# LPCB235_-_DAC.net
KiCad netlist of a schematic drawn in Altium Designer
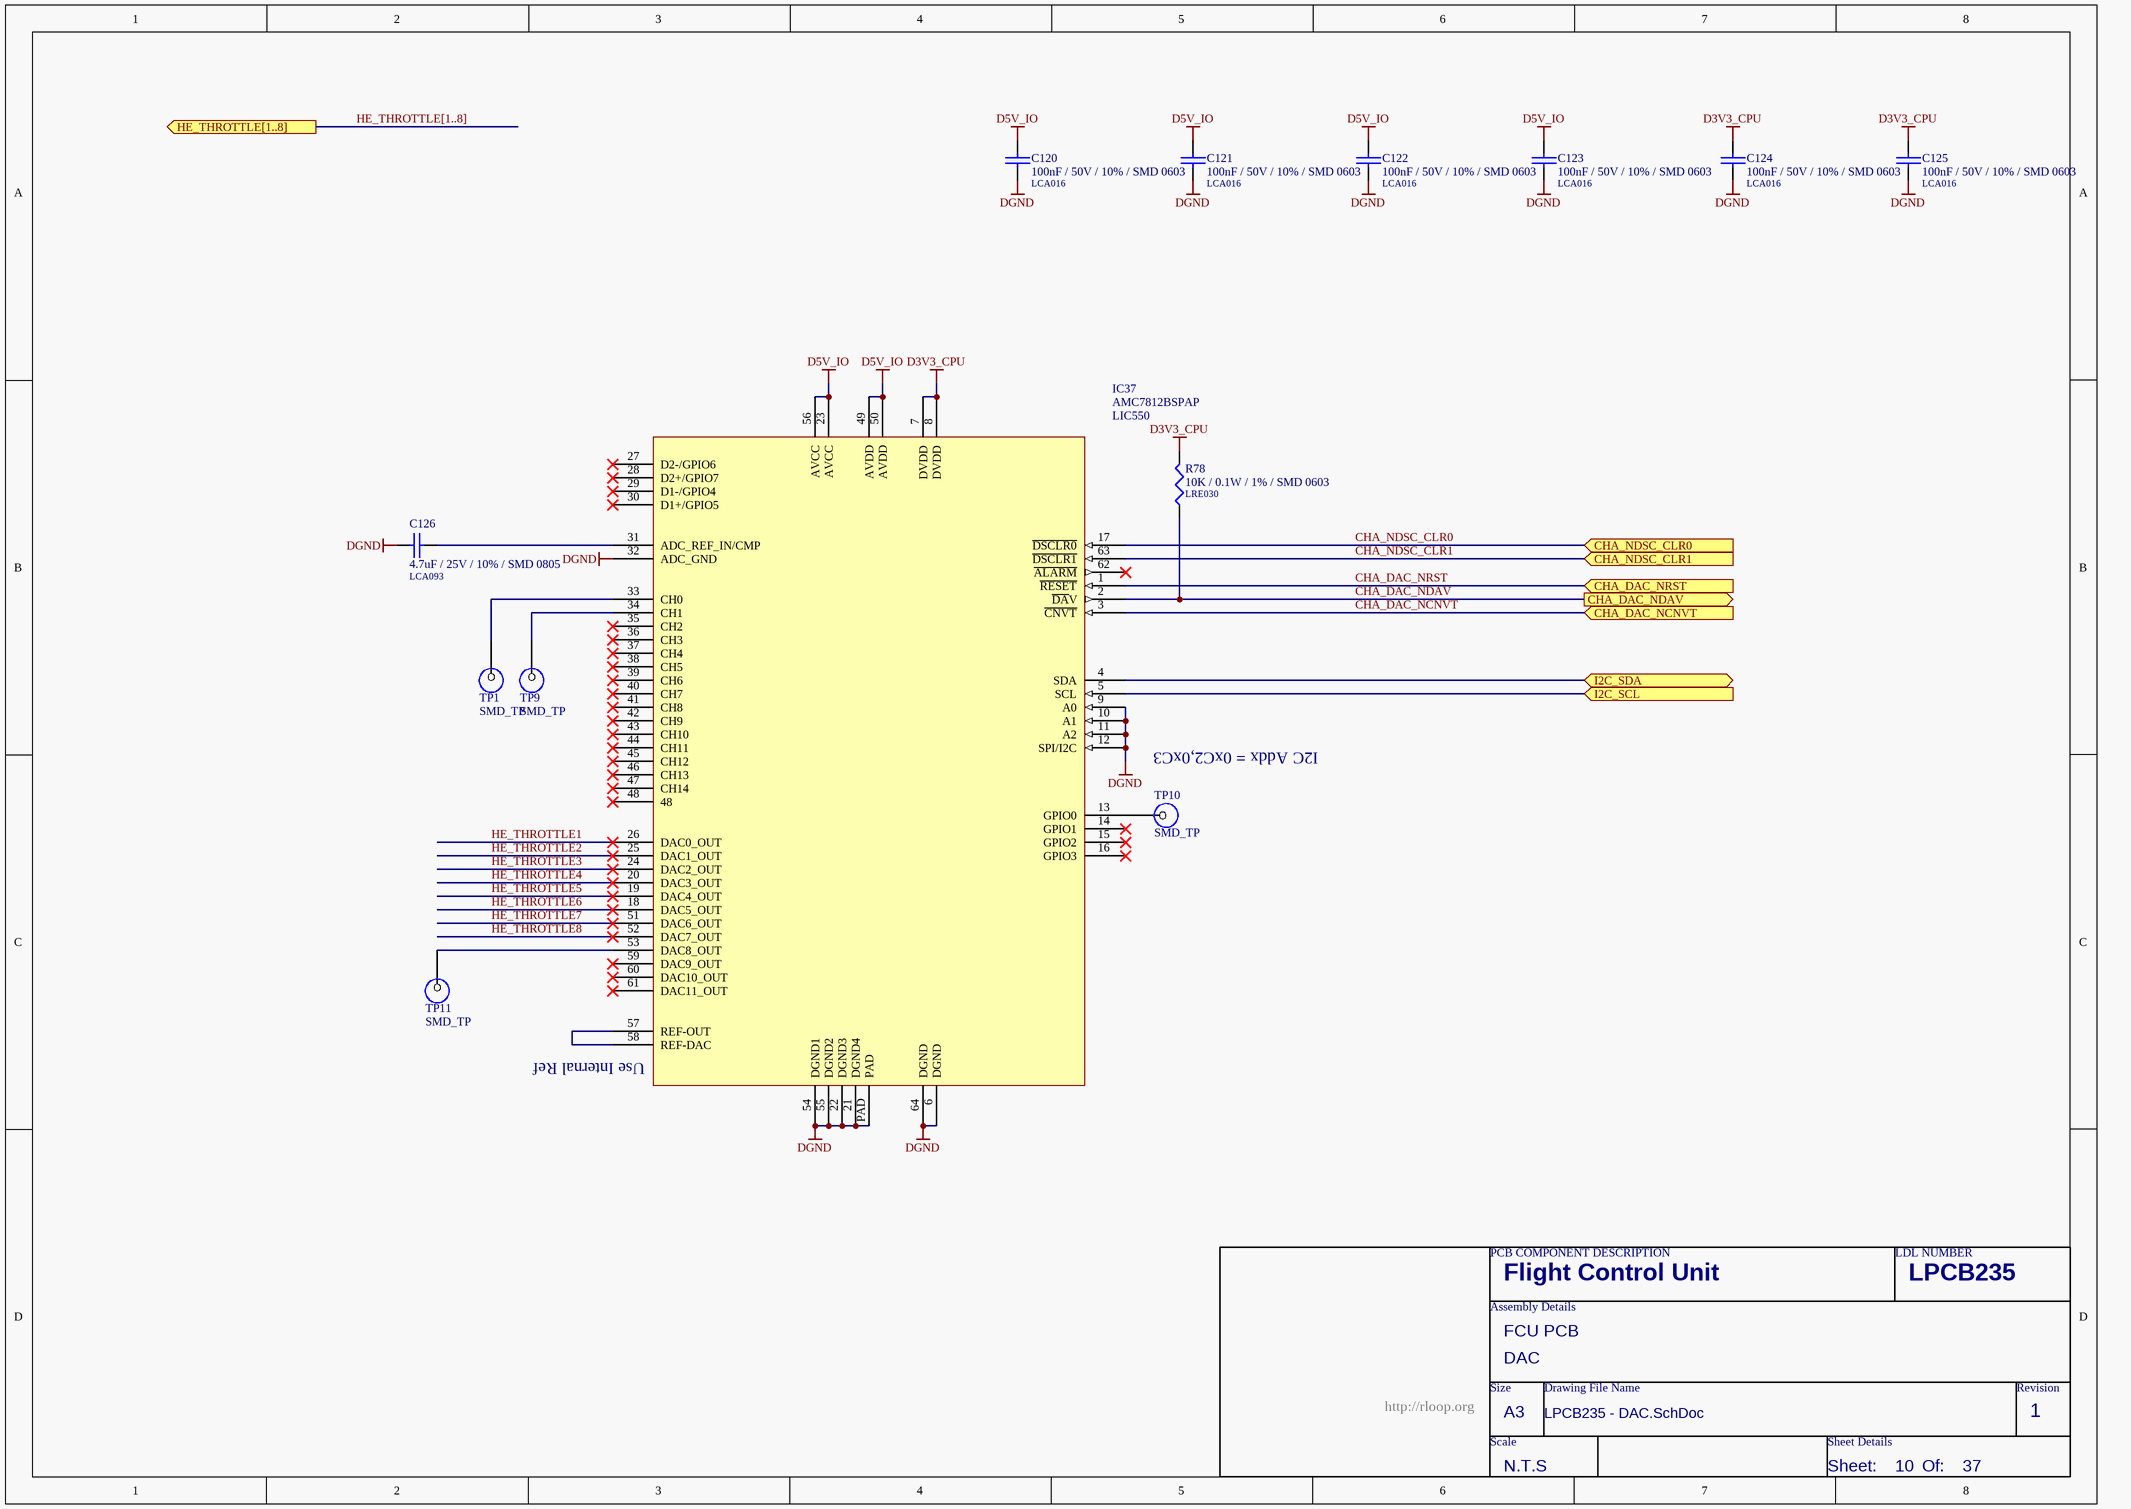
[diagram p0: LPCB235 - DAC.SchDoc]

(export (version "E")
  (design (tool "Eeschema 10.0.6"))
  (components
    (comp (ref "C120")
      (value "100nF / 50V / 10% / SMD 0603")
      (footprint "LFP011__CC1608-0603-IPC7351_B")
      (description "Capacitor, Ceramic Chip, 100nF (0.1uF), 50V, 5%, SMD 0603 [LCA016]")
      (fields (field (name "LDL_NUMBER") "LCA016"))
      (libsource (lib "LDL_Capacitors") (part "100nF / 50V / 10% / SMD 0603"))
    )
    (comp (ref "C121")
      (value "100nF / 50V / 10% / SMD 0603")
      (footprint "LFP011__CC1608-0603-IPC7351_B")
      (description "Capacitor, Ceramic Chip, 100nF (0.1uF), 50V, 5%, SMD 0603 [LCA016]")
      (fields (field (name "LDL_NUMBER") "LCA016"))
      (libsource (lib "LDL_Capacitors") (part "100nF / 50V / 10% / SMD 0603"))
    )
    (comp (ref "C122")
      (value "100nF / 50V / 10% / SMD 0603")
      (footprint "LFP011__CC1608-0603-IPC7351_B")
      (description "Capacitor, Ceramic Chip, 100nF (0.1uF), 50V, 5%, SMD 0603 [LCA016]")
      (fields (field (name "LDL_NUMBER") "LCA016"))
      (libsource (lib "LDL_Capacitors") (part "100nF / 50V / 10% / SMD 0603"))
    )
    (comp (ref "C123")
      (value "100nF / 50V / 10% / SMD 0603")
      (footprint "LFP011__CC1608-0603-IPC7351_B")
      (description "Capacitor, Ceramic Chip, 100nF (0.1uF), 50V, 5%, SMD 0603 [LCA016]")
      (fields (field (name "LDL_NUMBER") "LCA016"))
      (libsource (lib "LDL_Capacitors") (part "100nF / 50V / 10% / SMD 0603"))
    )
    (comp (ref "C124")
      (value "100nF / 50V / 10% / SMD 0603")
      (footprint "LFP011__CC1608-0603-IPC7351_B")
      (description "Capacitor, Ceramic Chip, 100nF (0.1uF), 50V, 5%, SMD 0603 [LCA016]")
      (fields (field (name "LDL_NUMBER") "LCA016"))
      (libsource (lib "LDL_Capacitors") (part "100nF / 50V / 10% / SMD 0603"))
    )
    (comp (ref "C125")
      (value "100nF / 50V / 10% / SMD 0603")
      (footprint "LFP011__CC1608-0603-IPC7351_B")
      (description "Capacitor, Ceramic Chip, 100nF (0.1uF), 50V, 5%, SMD 0603 [LCA016]")
      (fields (field (name "LDL_NUMBER") "LCA016"))
      (libsource (lib "LDL_Capacitors") (part "100nF / 50V / 10% / SMD 0603"))
    )
    (comp (ref "C126")
      (value "4.7uF / 25V / 10% / SMD 0805")
      (footprint "LFP010__CC2012-0805-IPC7351_B")
      (description "Capacitor, Ceramic Chip, 4.7uF, 25V, 10%, SMD 0805 [LCA093]")
      (fields (field (name "LDL_NUMBER") "LCA093"))
      (libsource (lib "LDL_Capacitors") (part "4.7uF / 25V / 10% / SMD 0805"))
    )
    (comp (ref "IC37")
      (value "AMC7812BSPAP")
      (footprint "LFP134__H-QFP10X10-64N")
      (description "IC, ADC / DAC, SMD [LIC550]")
      (fields (field (name "LDL_NUMBER") "LIC550"))
      (libsource (lib "LDL_Semiconductors") (part "AMC7812BSPAP"))
    )
    (comp (ref "R78")
      (value "10K / 0.1W / 1% / SMD 0603")
      (footprint "LFP020__CR1608-0603-IPC7351_B")
      (description "Resistor, Ceramic Chip, 10K, 0.1W, 1%, SMD 0603 [LRE030]")
      (fields (field (name "LDL_NUMBER") "LRE030"))
      (libsource (lib "LDL_Resistors") (part "10K / 0.1W / 1% / SMD 0603"))
    )
    (comp (ref "TP1")
      (value "SMD_TP")
      (footprint "SMD-TP")
      (description "SMD Test Point")
      (libsource (lib "LDL_Connectors") (part "SMD_TP"))
    )
    (comp (ref "TP9")
      (value "SMD_TP")
      (footprint "SMD-TP")
      (description "SMD Test Point")
      (libsource (lib "LDL_Connectors") (part "SMD_TP"))
    )
    (comp (ref "TP10")
      (value "SMD_TP")
      (footprint "SMD-TP")
      (description "SMD Test Point")
      (libsource (lib "LDL_Connectors") (part "SMD_TP"))
    )
    (comp (ref "TP11")
      (value "SMD_TP")
      (footprint "SMD-TP")
      (description "SMD Test Point")
      (libsource (lib "LDL_Connectors") (part "SMD_TP"))
    )
  )
  (nets
    (net (code "1") (name "/CHA_DAC_NCNVT") (class "Default")
      (node (ref "IC37") (pin "3") (pinfunction "~{CNVT}_3") (pintype "input"))
    )
    (net (code "2") (name "/CHA_DAC_NDAV") (class "Default")
      (node (ref "IC37") (pin "2") (pinfunction "~{DA}V_2") (pintype "output"))
      (node (ref "R78") (pin "1") (pintype "passive"))
    )
    (net (code "3") (name "/CHA_DAC_NRST") (class "Default")
      (node (ref "IC37") (pin "1") (pinfunction "~{RESET}_1") (pintype "input"))
    )
    (net (code "4") (name "/CHA_NDSC_CLR0") (class "Default")
      (node (ref "IC37") (pin "17") (pinfunction "~{DSCLR0}_17") (pintype "input"))
    )
    (net (code "5") (name "/CHA_NDSC_CLR1") (class "Default")
      (node (ref "IC37") (pin "63") (pinfunction "~{DSCLR1}_63") (pintype "input"))
    )
    (net (code "6") (name "/HE_THROTTLE1") (class "Default")
      (node (ref "IC37") (pin "26") (pinfunction "DAC0_OUT_26") (pintype "passive+no_connect"))
    )
    (net (code "7") (name "/HE_THROTTLE2") (class "Default")
      (node (ref "IC37") (pin "25") (pinfunction "DAC1_OUT_25") (pintype "passive+no_connect"))
    )
    (net (code "8") (name "/HE_THROTTLE3") (class "Default")
      (node (ref "IC37") (pin "24") (pinfunction "DAC2_OUT_24") (pintype "passive+no_connect"))
    )
    (net (code "9") (name "/HE_THROTTLE4") (class "Default")
      (node (ref "IC37") (pin "20") (pinfunction "DAC3_OUT_20") (pintype "passive+no_connect"))
    )
    (net (code "10") (name "/HE_THROTTLE5") (class "Default")
      (node (ref "IC37") (pin "19") (pinfunction "DAC4_OUT_19") (pintype "passive+no_connect"))
    )
    (net (code "11") (name "/HE_THROTTLE6") (class "Default")
      (node (ref "IC37") (pin "18") (pinfunction "DAC5_OUT_18") (pintype "passive+no_connect"))
    )
    (net (code "12") (name "/HE_THROTTLE7") (class "Default")
      (node (ref "IC37") (pin "51") (pinfunction "DAC6_OUT_51") (pintype "passive+no_connect"))
    )
    (net (code "13") (name "/HE_THROTTLE8") (class "Default")
      (node (ref "IC37") (pin "52") (pinfunction "DAC7_OUT_52") (pintype "passive+no_connect"))
    )
    (net (code "15") (name "/I2C_SCL") (class "Default")
      (node (ref "IC37") (pin "5") (pinfunction "SCL_5") (pintype "input"))
    )
    (net (code "16") (name "/I2C_SDA") (class "Default")
      (node (ref "IC37") (pin "4") (pinfunction "SDA_4") (pintype "passive"))
    )
    (net (code "17") (name "D3V3_CPU") (class "Default")
      (node (ref "C124") (pin "1") (pintype "passive"))
      (node (ref "C125") (pin "1") (pintype "passive"))
      (node (ref "IC37") (pin "7") (pinfunction "DVDD_7") (pintype "power_in"))
      (node (ref "IC37") (pin "8") (pinfunction "DVDD_8") (pintype "power_in"))
      (node (ref "R78") (pin "2") (pintype "passive"))
    )
    (net (code "18") (name "D5V_IO") (class "Default")
      (node (ref "C120") (pin "1") (pintype "passive"))
      (node (ref "C121") (pin "1") (pintype "passive"))
      (node (ref "C122") (pin "1") (pintype "passive"))
      (node (ref "C123") (pin "1") (pintype "passive"))
      (node (ref "IC37") (pin "23") (pinfunction "AVCC_23") (pintype "power_in"))
      (node (ref "IC37") (pin "49") (pinfunction "AVDD_49") (pintype "power_in"))
      (node (ref "IC37") (pin "50") (pinfunction "AVDD_50") (pintype "power_in"))
      (node (ref "IC37") (pin "56") (pinfunction "AVCC_56") (pintype "power_in"))
    )
    (net (code "19") (name "DGND") (class "Default")
      (node (ref "C120") (pin "2") (pintype "passive"))
      (node (ref "C121") (pin "2") (pintype "passive"))
      (node (ref "C122") (pin "2") (pintype "passive"))
      (node (ref "C123") (pin "2") (pintype "passive"))
      (node (ref "C124") (pin "2") (pintype "passive"))
      (node (ref "C125") (pin "2") (pintype "passive"))
      (node (ref "C126") (pin "1") (pintype "passive"))
      (node (ref "IC37") (pin "10") (pinfunction "A1_10") (pintype "input"))
      (node (ref "IC37") (pin "11") (pinfunction "A2_11") (pintype "input"))
      (node (ref "IC37") (pin "12") (pinfunction "SPI/I2C_12") (pintype "input"))
      (node (ref "IC37") (pin "21") (pinfunction "DGND4_21") (pintype "power_in"))
      (node (ref "IC37") (pin "22") (pinfunction "DGND3_22") (pintype "power_in"))
      (node (ref "IC37") (pin "32") (pinfunction "ADC_GND_32") (pintype "power_in"))
      (node (ref "IC37") (pin "54") (pinfunction "DGND1_54") (pintype "power_in"))
      (node (ref "IC37") (pin "55") (pinfunction "DGND2_55") (pintype "power_in"))
      (node (ref "IC37") (pin "6") (pinfunction "DGND_6") (pintype "power_in"))
      (node (ref "IC37") (pin "64") (pinfunction "DGND_64") (pintype "power_in"))
      (node (ref "IC37") (pin "9") (pinfunction "A0_9") (pintype "input"))
      (node (ref "IC37") (pin "PAD") (pinfunction "PAD_PAD") (pintype "power_in"))
    )
    (net (code "20") (name "Net-(IC37-ADC_REF_IN{slash}CMP)") (class "Default")
      (node (ref "C126") (pin "2") (pintype "passive"))
      (node (ref "IC37") (pin "31") (pinfunction "ADC_REF_IN/CMP_31") (pintype "passive"))
    )
    (net (code "21") (name "Net-(IC37-CH0)") (class "Default")
      (node (ref "IC37") (pin "33") (pinfunction "CH0_33") (pintype "passive"))
      (node (ref "TP1") (pin "1") (pintype "passive"))
    )
    (net (code "22") (name "Net-(IC37-CH1)") (class "Default")
      (node (ref "IC37") (pin "34") (pinfunction "CH1_34") (pintype "passive"))
      (node (ref "TP9") (pin "1") (pintype "passive"))
    )
    (net (code "23") (name "Net-(IC37-DAC8_OUT)") (class "Default")
      (node (ref "IC37") (pin "53") (pinfunction "DAC8_OUT_53") (pintype "passive"))
      (node (ref "TP11") (pin "1") (pintype "passive"))
    )
    (net (code "24") (name "Net-(IC37-GPIO0)") (class "Default")
      (node (ref "IC37") (pin "13") (pinfunction "GPIO0_13") (pintype "passive"))
      (node (ref "TP10") (pin "1") (pintype "passive"))
    )
    (net (code "25") (name "Net-(IC37-REF-DAC)") (class "Default")
      (node (ref "IC37") (pin "57") (pinfunction "REF-OUT_57") (pintype "passive"))
      (node (ref "IC37") (pin "58") (pinfunction "REF-DAC_58") (pintype "passive"))
    )
    (net (code "26") (name "unconnected-(IC37-CH2-Pad35)") (class "Default")
      (node (ref "IC37") (pin "35") (pinfunction "CH2_35") (pintype "passive+no_connect"))
    )
    (net (code "27") (name "unconnected-(IC37-CH3-Pad36)") (class "Default")
      (node (ref "IC37") (pin "36") (pinfunction "CH3_36") (pintype "passive+no_connect"))
    )
    (net (code "28") (name "unconnected-(IC37-CH4-Pad37)") (class "Default")
      (node (ref "IC37") (pin "37") (pinfunction "CH4_37") (pintype "passive+no_connect"))
    )
    (net (code "29") (name "unconnected-(IC37-CH5-Pad38)") (class "Default")
      (node (ref "IC37") (pin "38") (pinfunction "CH5_38") (pintype "passive+no_connect"))
    )
    (net (code "30") (name "unconnected-(IC37-CH6-Pad39)") (class "Default")
      (node (ref "IC37") (pin "39") (pinfunction "CH6_39") (pintype "passive+no_connect"))
    )
    (net (code "31") (name "unconnected-(IC37-CH7-Pad40)") (class "Default")
      (node (ref "IC37") (pin "40") (pinfunction "CH7_40") (pintype "passive+no_connect"))
    )
    (net (code "32") (name "unconnected-(IC37-CH8-Pad41)") (class "Default")
      (node (ref "IC37") (pin "41") (pinfunction "CH8_41") (pintype "passive+no_connect"))
    )
    (net (code "33") (name "unconnected-(IC37-CH9-Pad42)") (class "Default")
      (node (ref "IC37") (pin "42") (pinfunction "CH9_42") (pintype "passive+no_connect"))
    )
    (net (code "34") (name "unconnected-(IC37-CH10-Pad43)") (class "Default")
      (node (ref "IC37") (pin "43") (pinfunction "CH10_43") (pintype "passive+no_connect"))
    )
    (net (code "35") (name "unconnected-(IC37-CH11-Pad44)") (class "Default")
      (node (ref "IC37") (pin "44") (pinfunction "CH11_44") (pintype "passive+no_connect"))
    )
    (net (code "36") (name "unconnected-(IC37-CH12-Pad45)") (class "Default")
      (node (ref "IC37") (pin "45") (pinfunction "CH12_45") (pintype "passive+no_connect"))
    )
    (net (code "37") (name "unconnected-(IC37-CH13-Pad46)") (class "Default")
      (node (ref "IC37") (pin "46") (pinfunction "CH13_46") (pintype "passive+no_connect"))
    )
    (net (code "38") (name "unconnected-(IC37-CH14-Pad47)") (class "Default")
      (node (ref "IC37") (pin "47") (pinfunction "CH14_47") (pintype "passive+no_connect"))
    )
    (net (code "39") (name "unconnected-(IC37-D1+{slash}GPIO5-Pad30)") (class "Default")
      (node (ref "IC37") (pin "30") (pinfunction "D1+/GPIO5_30") (pintype "passive+no_connect"))
    )
    (net (code "40") (name "unconnected-(IC37-D1-{slash}GPIO4-Pad29)") (class "Default")
      (node (ref "IC37") (pin "29") (pinfunction "D1-/GPIO4_29") (pintype "passive+no_connect"))
    )
    (net (code "41") (name "unconnected-(IC37-D2+{slash}GPIO7-Pad28)") (class "Default")
      (node (ref "IC37") (pin "28") (pinfunction "D2+/GPIO7_28") (pintype "passive+no_connect"))
    )
    (net (code "42") (name "unconnected-(IC37-D2-{slash}GPIO6-Pad27)") (class "Default")
      (node (ref "IC37") (pin "27") (pinfunction "D2-/GPIO6_27") (pintype "passive+no_connect"))
    )
    (net (code "43") (name "unconnected-(IC37-DAC9_OUT-Pad59)") (class "Default")
      (node (ref "IC37") (pin "59") (pinfunction "DAC9_OUT_59") (pintype "passive+no_connect"))
    )
    (net (code "44") (name "unconnected-(IC37-DAC10_OUT-Pad60)") (class "Default")
      (node (ref "IC37") (pin "60") (pinfunction "DAC10_OUT_60") (pintype "passive+no_connect"))
    )
    (net (code "45") (name "unconnected-(IC37-DAC11_OUT-Pad61)") (class "Default")
      (node (ref "IC37") (pin "61") (pinfunction "DAC11_OUT_61") (pintype "passive+no_connect"))
    )
    (net (code "46") (name "unconnected-(IC37-GPIO1-Pad14)") (class "Default")
      (node (ref "IC37") (pin "14") (pinfunction "GPIO1_14") (pintype "passive+no_connect"))
    )
    (net (code "47") (name "unconnected-(IC37-GPIO2-Pad15)") (class "Default")
      (node (ref "IC37") (pin "15") (pinfunction "GPIO2_15") (pintype "passive+no_connect"))
    )
    (net (code "48") (name "unconnected-(IC37-GPIO3-Pad16)") (class "Default")
      (node (ref "IC37") (pin "16") (pinfunction "GPIO3_16") (pintype "passive+no_connect"))
    )
    (net (code "49") (name "unconnected-(IC37-Pad48)") (class "Default")
      (node (ref "IC37") (pin "48") (pinfunction "48_48") (pintype "passive+no_connect"))
    )
    (net (code "50") (name "unconnected-(IC37-~{ALARM}-Pad62)") (class "Default")
      (node (ref "IC37") (pin "62") (pinfunction "~{ALARM}_62") (pintype "output+no_connect"))
    )
  )
)
